# 12_RK3588_DDR_Controler.net
KiCad netlist of a schematic drawn in Altium Designer
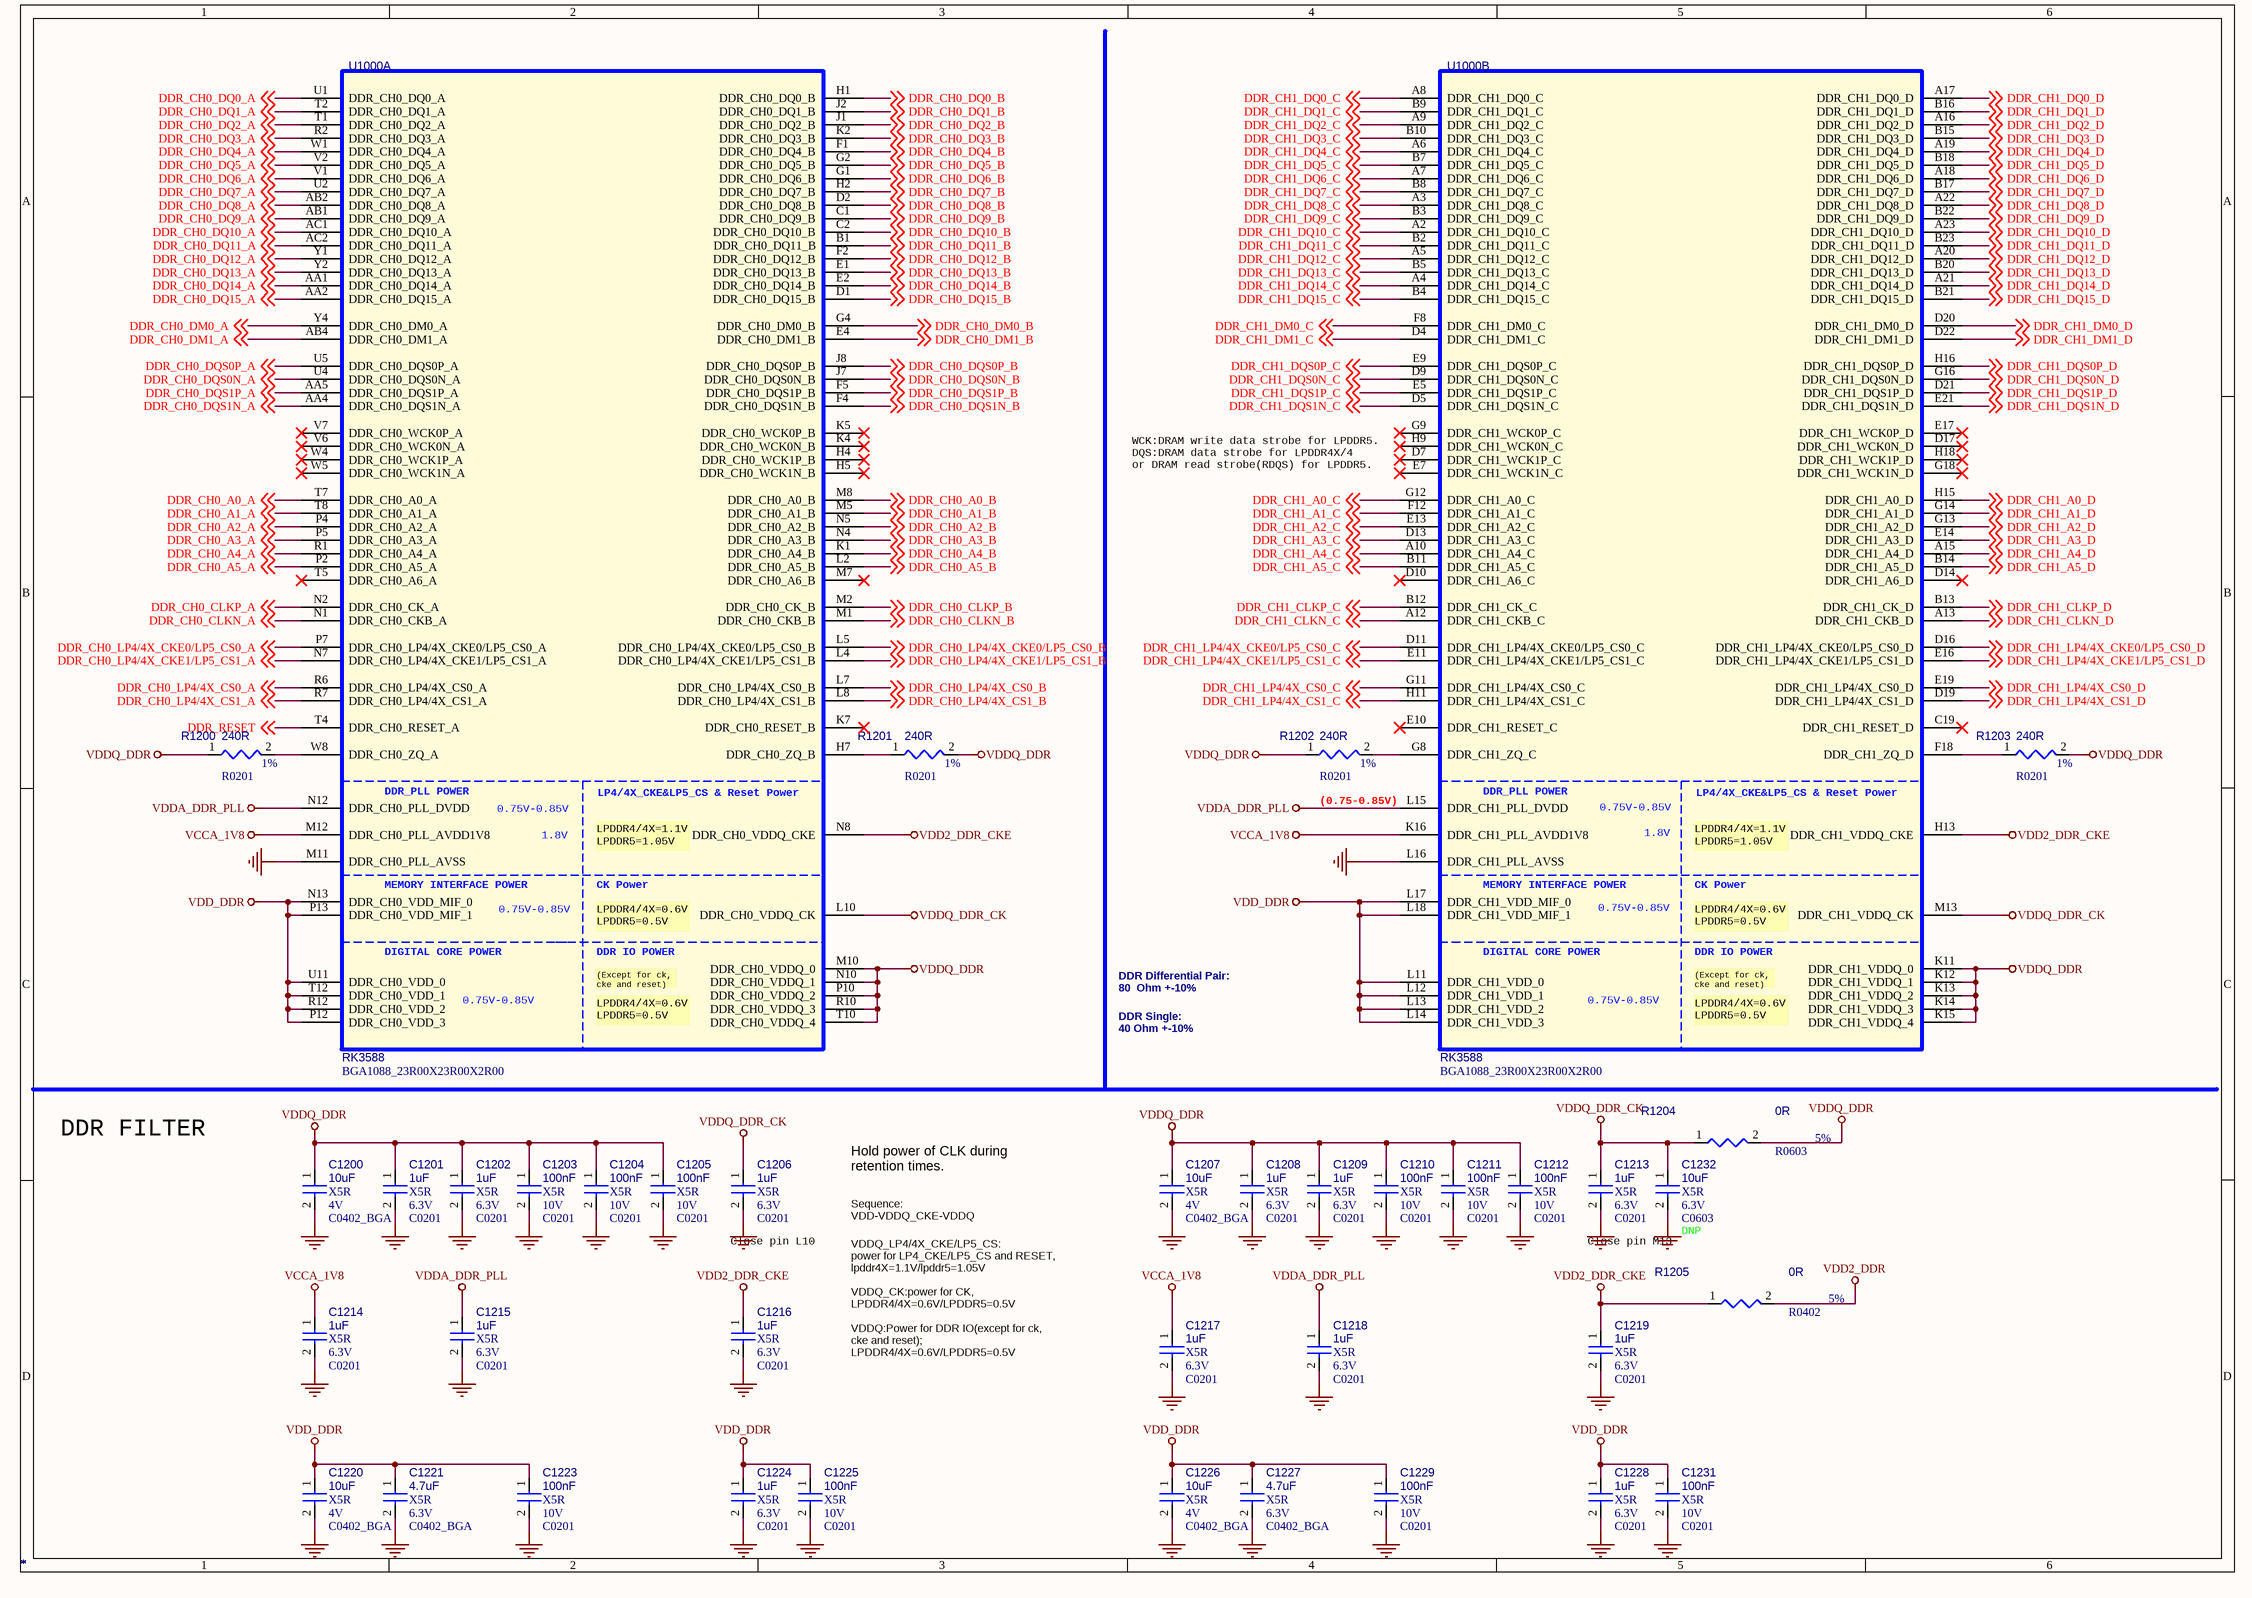
[diagram p0: 12.RK3588 DDR Controler.SchDoc]

(export (version "E")
  (design (tool "Eeschema 10.0.6"))
  (components
    (comp (ref "C1200")
      (value "*")
      (footprint "C0402_BGA")
      (description "cap,10.00uF,+/-20%,4V,X5R,C0402")
      (fields
        (field (name "VOLTAGE") "4V")
        (field (name "PCB FOOTPRINT") "C0402_BGA")
        (field (name "DIELECTRIC") "X5R")
        (field (name "MANUFACTURER") "YAGEO")
        (field (name "TOLERANCE") "20%")
        (field (name "ALTIUM_UNNAMED_1") "10uF")
        (field (name "CREATED BY") "JJJ")
      )
      (libsource (lib "*") (part "CAP NP"))
    )
    (comp (ref "C1201")
      (value "*")
      (footprint "C0201")
      (description "cap,1.00uF,+/-20%,6.3V,X5R,C0201")
      (fields
        (field (name "VOLTAGE") "6.3V")
        (field (name "PCB FOOTPRINT") "C0201")
        (field (name "DIELECTRIC") "X5R")
        (field (name "MANUFACTURER") "TDK")
        (field (name "TOLERANCE") "20%")
        (field (name "ALTIUM_UNNAMED_1") "1uF")
        (field (name "CREATED BY") "JJJ")
      )
      (libsource (lib "*") (part "CAP NP"))
    )
    (comp (ref "C1202")
      (value "*")
      (footprint "C0201")
      (description "cap,1.00uF,+/-20%,6.3V,X5R,C0201")
      (fields
        (field (name "VOLTAGE") "6.3V")
        (field (name "PCB FOOTPRINT") "C0201")
        (field (name "DIELECTRIC") "X5R")
        (field (name "TOLERANCE") "20%")
        (field (name "MANUFACTURER") "TDK")
        (field (name "ALTIUM_UNNAMED_1") "1uF")
        (field (name "CREATED BY") "JJJ")
      )
      (libsource (lib "*") (part "CAP NP"))
    )
    (comp (ref "C1203")
      (value "*")
      (footprint "C0201")
      (description "cap,100.00nF,+/-10%,10V,X5R,C0201")
      (fields
        (field (name "VOLTAGE") "10V")
        (field (name "PCB FOOTPRINT") "C0201")
        (field (name "DIELECTRIC") "X5R")
        (field (name "TOLERANCE") "10%")
        (field (name "MANUFACTURER") "TDK")
        (field (name "ALTIUM_UNNAMED_1") "100nF")
        (field (name "CREATED BY") "JJJ")
      )
      (libsource (lib "*") (part "CAP NP"))
    )
    (comp (ref "C1204")
      (value "*")
      (footprint "C0201")
      (description "cap,100.00nF,+/-10%,10V,X5R,C0201")
      (fields
        (field (name "VOLTAGE") "10V")
        (field (name "PCB FOOTPRINT") "C0201")
        (field (name "DIELECTRIC") "X5R")
        (field (name "TOLERANCE") "10%")
        (field (name "MANUFACTURER") "TDK")
        (field (name "ALTIUM_UNNAMED_1") "100nF")
        (field (name "CREATED BY") "JJJ")
      )
      (libsource (lib "*") (part "CAP NP"))
    )
    (comp (ref "C1205")
      (value "*")
      (footprint "C0201")
      (description "cap,100.00nF,+/-10%,10V,X5R,C0201")
      (fields
        (field (name "VOLTAGE") "10V")
        (field (name "PCB FOOTPRINT") "C0201")
        (field (name "DIELECTRIC") "X5R")
        (field (name "TOLERANCE") "10%")
        (field (name "MANUFACTURER") "TDK")
        (field (name "ALTIUM_UNNAMED_1") "100nF")
        (field (name "CREATED BY") "JJJ")
      )
      (libsource (lib "*") (part "CAP NP"))
    )
    (comp (ref "C1206")
      (value "*")
      (footprint "C0201")
      (description "cap,1.00uF,+/-20%,6.3V,X5R,C0201")
      (fields
        (field (name "VOLTAGE") "6.3V")
        (field (name "PCB FOOTPRINT") "C0201")
        (field (name "DIELECTRIC") "X5R")
        (field (name "MANUFACTURER") "TDK")
        (field (name "TOLERANCE") "20%")
        (field (name "ALTIUM_UNNAMED_1") "1uF")
        (field (name "CREATED BY") "JJJ")
      )
      (libsource (lib "*") (part "CAP NP"))
    )
    (comp (ref "C1207")
      (value "*")
      (footprint "C0402_BGA")
      (description "cap,10.00uF,+/-20%,4V,X5R,C0402")
      (fields
        (field (name "VOLTAGE") "4V")
        (field (name "PCB FOOTPRINT") "C0402_BGA")
        (field (name "DIELECTRIC") "X5R")
        (field (name "MANUFACTURER") "YAGEO")
        (field (name "TOLERANCE") "20%")
        (field (name "ALTIUM_UNNAMED_1") "10uF")
        (field (name "CREATED BY") "JJJ")
      )
      (libsource (lib "*") (part "CAP NP"))
    )
    (comp (ref "C1208")
      (value "*")
      (footprint "C0201")
      (description "cap,1.00uF,+/-20%,6.3V,X5R,C0201")
      (fields
        (field (name "VOLTAGE") "6.3V")
        (field (name "PCB FOOTPRINT") "C0201")
        (field (name "DIELECTRIC") "X5R")
        (field (name "MANUFACTURER") "TDK")
        (field (name "TOLERANCE") "20%")
        (field (name "ALTIUM_UNNAMED_1") "1uF")
        (field (name "CREATED BY") "JJJ")
      )
      (libsource (lib "*") (part "CAP NP"))
    )
    (comp (ref "C1209")
      (value "*")
      (footprint "C0201")
      (description "cap,1.00uF,+/-20%,6.3V,X5R,C0201")
      (fields
        (field (name "VOLTAGE") "6.3V")
        (field (name "PCB FOOTPRINT") "C0201")
        (field (name "DIELECTRIC") "X5R")
        (field (name "TOLERANCE") "20%")
        (field (name "MANUFACTURER") "TDK")
        (field (name "ALTIUM_UNNAMED_1") "1uF")
        (field (name "CREATED BY") "JJJ")
      )
      (libsource (lib "*") (part "CAP NP"))
    )
    (comp (ref "C1210")
      (value "*")
      (footprint "C0201")
      (description "cap,100.00nF,+/-10%,10V,X5R,C0201")
      (fields
        (field (name "VOLTAGE") "10V")
        (field (name "PCB FOOTPRINT") "C0201")
        (field (name "DIELECTRIC") "X5R")
        (field (name "TOLERANCE") "10%")
        (field (name "MANUFACTURER") "TDK")
        (field (name "ALTIUM_UNNAMED_1") "100nF")
        (field (name "CREATED BY") "JJJ")
      )
      (libsource (lib "*") (part "CAP NP"))
    )
    (comp (ref "C1211")
      (value "*")
      (footprint "C0201")
      (description "cap,100.00nF,+/-10%,10V,X5R,C0201")
      (fields
        (field (name "VOLTAGE") "10V")
        (field (name "PCB FOOTPRINT") "C0201")
        (field (name "DIELECTRIC") "X5R")
        (field (name "TOLERANCE") "10%")
        (field (name "MANUFACTURER") "TDK")
        (field (name "ALTIUM_UNNAMED_1") "100nF")
        (field (name "CREATED BY") "JJJ")
      )
      (libsource (lib "*") (part "CAP NP"))
    )
    (comp (ref "C1212")
      (value "*")
      (footprint "C0201")
      (description "cap,100.00nF,+/-10%,10V,X5R,C0201")
      (fields
        (field (name "VOLTAGE") "10V")
        (field (name "PCB FOOTPRINT") "C0201")
        (field (name "DIELECTRIC") "X5R")
        (field (name "TOLERANCE") "10%")
        (field (name "MANUFACTURER") "TDK")
        (field (name "ALTIUM_UNNAMED_1") "100nF")
        (field (name "CREATED BY") "JJJ")
      )
      (libsource (lib "*") (part "CAP NP"))
    )
    (comp (ref "C1213")
      (value "*")
      (footprint "C0201")
      (description "cap,1.00uF,+/-20%,6.3V,X5R,C0201")
      (fields
        (field (name "VOLTAGE") "6.3V")
        (field (name "PCB FOOTPRINT") "C0201")
        (field (name "DIELECTRIC") "X5R")
        (field (name "MANUFACTURER") "TDK")
        (field (name "TOLERANCE") "20%")
        (field (name "ALTIUM_UNNAMED_1") "1uF")
        (field (name "CREATED BY") "JJJ")
      )
      (libsource (lib "*") (part "CAP NP"))
    )
    (comp (ref "C1214")
      (value "*")
      (footprint "C0201")
      (description "cap,1.00uF,+/-20%,6.3V,X5R,C0201")
      (fields
        (field (name "VOLTAGE") "6.3V")
        (field (name "PCB FOOTPRINT") "C0201")
        (field (name "DIELECTRIC") "X5R")
        (field (name "TOLERANCE") "20%")
        (field (name "MANUFACTURER") "TDK")
        (field (name "ALTIUM_UNNAMED_1") "1uF")
        (field (name "CREATED BY") "JJJ")
      )
      (libsource (lib "*") (part "CAP NP"))
    )
    (comp (ref "C1215")
      (value "*")
      (footprint "C0201")
      (description "cap,1.00uF,+/-20%,6.3V,X5R,C0201")
      (fields
        (field (name "VOLTAGE") "6.3V")
        (field (name "PCB FOOTPRINT") "C0201")
        (field (name "DIELECTRIC") "X5R")
        (field (name "MANUFACTURER") "TDK")
        (field (name "TOLERANCE") "20%")
        (field (name "ALTIUM_UNNAMED_1") "1uF")
        (field (name "CREATED BY") "JJJ")
      )
      (libsource (lib "*") (part "CAP NP"))
    )
    (comp (ref "C1216")
      (value "*")
      (footprint "C0201")
      (description "cap,1.00uF,+/-20%,6.3V,X5R,C0201")
      (fields
        (field (name "VOLTAGE") "6.3V")
        (field (name "PCB FOOTPRINT") "C0201")
        (field (name "DIELECTRIC") "X5R")
        (field (name "MANUFACTURER") "TDK")
        (field (name "TOLERANCE") "20%")
        (field (name "ALTIUM_UNNAMED_1") "1uF")
        (field (name "CREATED BY") "JJJ")
      )
      (libsource (lib "*") (part "CAP NP"))
    )
    (comp (ref "C1217")
      (value "*")
      (footprint "C0201")
      (description "cap,1.00uF,+/-20%,6.3V,X5R,C0201")
      (fields
        (field (name "VOLTAGE") "6.3V")
        (field (name "PCB FOOTPRINT") "C0201")
        (field (name "DIELECTRIC") "X5R")
        (field (name "MANUFACTURER") "TDK")
        (field (name "TOLERANCE") "20%")
        (field (name "ALTIUM_UNNAMED_1") "1uF")
        (field (name "CREATED BY") "JJJ")
      )
      (libsource (lib "*") (part "CAP NP"))
    )
    (comp (ref "C1218")
      (value "*")
      (footprint "C0201")
      (description "cap,1.00uF,+/-20%,6.3V,X5R,C0201")
      (fields
        (field (name "VOLTAGE") "6.3V")
        (field (name "PCB FOOTPRINT") "C0201")
        (field (name "DIELECTRIC") "X5R")
        (field (name "TOLERANCE") "20%")
        (field (name "MANUFACTURER") "TDK")
        (field (name "ALTIUM_UNNAMED_1") "1uF")
        (field (name "CREATED BY") "JJJ")
      )
      (libsource (lib "*") (part "CAP NP"))
    )
    (comp (ref "C1219")
      (value "*")
      (footprint "C0201")
      (description "cap,1.00uF,+/-20%,6.3V,X5R,C0201")
      (fields
        (field (name "VOLTAGE") "6.3V")
        (field (name "PCB FOOTPRINT") "C0201")
        (field (name "DIELECTRIC") "X5R")
        (field (name "TOLERANCE") "20%")
        (field (name "MANUFACTURER") "TDK")
        (field (name "ALTIUM_UNNAMED_1") "1uF")
        (field (name "CREATED BY") "JJJ")
      )
      (libsource (lib "*") (part "CAP NP"))
    )
    (comp (ref "C1220")
      (value "*")
      (footprint "C0402_BGA")
      (description "cap,10.00uF,+/-20%,4V,X5R,C0402")
      (fields
        (field (name "VOLTAGE") "4V")
        (field (name "PCB FOOTPRINT") "C0402_BGA")
        (field (name "DIELECTRIC") "X5R")
        (field (name "TOLERANCE") "20%")
        (field (name "MANUFACTURER") "YAGEO")
        (field (name "ALTIUM_UNNAMED_1") "10uF")
        (field (name "CREATED BY") "JJJ")
      )
      (libsource (lib "*") (part "CAP NP"))
    )
    (comp (ref "C1221")
      (value "*")
      (footprint "C0402_BGA")
      (description "cap,4.70uF,+/-10%,6.3V,X5R,C0402")
      (fields
        (field (name "VOLTAGE") "6.3V")
        (field (name "PCB FOOTPRINT") "C0402_BGA")
        (field (name "DIELECTRIC") "X5R")
        (field (name "MANUFACTURER") "TDK")
        (field (name "TOLERANCE") "10%")
        (field (name "ALTIUM_UNNAMED_1") "4.7uF")
        (field (name "CREATED BY") "JJJ")
      )
      (libsource (lib "*") (part "CAP NP"))
    )
    (comp (ref "C1223")
      (value "*")
      (footprint "C0201")
      (description "cap,100.00nF,+/-10%,10V,X5R,C0201")
      (fields
        (field (name "VOLTAGE") "10V")
        (field (name "PCB FOOTPRINT") "C0201")
        (field (name "DIELECTRIC") "X5R")
        (field (name "TOLERANCE") "10%")
        (field (name "MANUFACTURER") "TDK")
        (field (name "ALTIUM_UNNAMED_1") "100nF")
        (field (name "CREATED BY") "JJJ")
      )
      (libsource (lib "*") (part "CAP NP"))
    )
    (comp (ref "C1224")
      (value "*")
      (footprint "C0201")
      (description "cap,1.00uF,+/-20%,6.3V,X5R,C0201")
      (fields
        (field (name "VOLTAGE") "6.3V")
        (field (name "PCB FOOTPRINT") "C0201")
        (field (name "DIELECTRIC") "X5R")
        (field (name "MANUFACTURER") "TDK")
        (field (name "TOLERANCE") "20%")
        (field (name "ALTIUM_UNNAMED_1") "1uF")
        (field (name "CREATED BY") "JJJ")
      )
      (libsource (lib "*") (part "CAP NP"))
    )
    (comp (ref "C1225")
      (value "*")
      (footprint "C0201")
      (description "cap,100.00nF,+/-10%,10V,X5R,C0201")
      (fields
        (field (name "VOLTAGE") "10V")
        (field (name "PCB FOOTPRINT") "C0201")
        (field (name "DIELECTRIC") "X5R")
        (field (name "TOLERANCE") "10%")
        (field (name "MANUFACTURER") "TDK")
        (field (name "ALTIUM_UNNAMED_1") "100nF")
        (field (name "CREATED BY") "JJJ")
      )
      (libsource (lib "*") (part "CAP NP"))
    )
    (comp (ref "C1226")
      (value "*")
      (footprint "C0402_BGA")
      (description "cap,10.00uF,+/-20%,4V,X5R,C0402")
      (fields
        (field (name "VOLTAGE") "4V")
        (field (name "PCB FOOTPRINT") "C0402_BGA")
        (field (name "DIELECTRIC") "X5R")
        (field (name "TOLERANCE") "20%")
        (field (name "MANUFACTURER") "YAGEO")
        (field (name "ALTIUM_UNNAMED_1") "10uF")
        (field (name "CREATED BY") "JJJ")
      )
      (libsource (lib "*") (part "CAP NP"))
    )
    (comp (ref "C1227")
      (value "*")
      (footprint "C0402_BGA")
      (description "cap,4.70uF,+/-10%,6.3V,X5R,C0402")
      (fields
        (field (name "VOLTAGE") "6.3V")
        (field (name "PCB FOOTPRINT") "C0402_BGA")
        (field (name "DIELECTRIC") "X5R")
        (field (name "MANUFACTURER") "TDK")
        (field (name "TOLERANCE") "10%")
        (field (name "ALTIUM_UNNAMED_1") "4.7uF")
        (field (name "CREATED BY") "JJJ")
      )
      (libsource (lib "*") (part "CAP NP"))
    )
    (comp (ref "C1228")
      (value "*")
      (footprint "C0201")
      (description "cap,1.00uF,+/-20%,6.3V,X5R,C0201")
      (fields
        (field (name "VOLTAGE") "6.3V")
        (field (name "PCB FOOTPRINT") "C0201")
        (field (name "DIELECTRIC") "X5R")
        (field (name "TOLERANCE") "20%")
        (field (name "MANUFACTURER") "TDK")
        (field (name "ALTIUM_UNNAMED_1") "1uF")
        (field (name "CREATED BY") "JJJ")
      )
      (libsource (lib "*") (part "CAP NP"))
    )
    (comp (ref "C1229")
      (value "*")
      (footprint "C0201")
      (description "cap,100.00nF,+/-10%,10V,X5R,C0201")
      (fields
        (field (name "VOLTAGE") "10V")
        (field (name "PCB FOOTPRINT") "C0201")
        (field (name "DIELECTRIC") "X5R")
        (field (name "TOLERANCE") "10%")
        (field (name "MANUFACTURER") "TDK")
        (field (name "ALTIUM_UNNAMED_1") "100nF")
        (field (name "CREATED BY") "JJJ")
      )
      (libsource (lib "*") (part "CAP NP"))
    )
    (comp (ref "C1231")
      (value "*")
      (footprint "C0201")
      (description "cap,100.00nF,+/-10%,10V,X5R,C0201")
      (fields
        (field (name "VOLTAGE") "10V")
        (field (name "PCB FOOTPRINT") "C0201")
        (field (name "DIELECTRIC") "X5R")
        (field (name "TOLERANCE") "10%")
        (field (name "MANUFACTURER") "TDK")
        (field (name "ALTIUM_UNNAMED_1") "100nF")
        (field (name "CREATED BY") "JJJ")
      )
      (libsource (lib "*") (part "CAP NP"))
    )
    (comp (ref "C1232")
      (value "*")
      (footprint "C0603")
      (description "cap,10.00uF,+/-10%,6.3V,X5R,C0603")
      (fields
        (field (name "VOLTAGE") "6.3V")
        (field (name "PCB FOOTPRINT") "C0603")
        (field (name "DIELECTRIC") "X5R")
        (field (name "OPTION") "DNP")
        (field (name "TOLERANCE") "10%")
        (field (name "MANUFACTURER") "TDK")
        (field (name "ALTIUM_UNNAMED_1") "10uF")
        (field (name "CREATED BY") "JJJ")
      )
      (libsource (lib "*") (part "CAP NP"))
    )
    (comp (ref "R1200")
      (value "*")
      (footprint "R0402")
      (description "НЁУГєсД¤µзЧи,240R,+/-1%,R0201,1/20W.")
      (fields
        (field (name "PCB FOOTPRINT") "R0201")
        (field (name "TOLERANCE") "1%")
        (field (name "MANUFACTURER") "YAGEO")
        (field (name "ALTIUM_UNNAMED_1") "240R")
        (field (name "CREATED BY") "YTL")
      )
      (libsource (lib "*") (part "RESISTOR_Dup1"))
    )
    (comp (ref "R1201")
      (value "*")
      (footprint "R0402")
      (description "НЁУГєсД¤µзЧи,240R,+/-1%,R0201,1/20W.")
      (fields
        (field (name "PCB FOOTPRINT") "R0201")
        (field (name "TOLERANCE") "1%")
        (field (name "MANUFACTURER") "YAGEO")
        (field (name "ALTIUM_UNNAMED_1") "240R")
        (field (name "CREATED BY") "YTL")
      )
      (libsource (lib "*") (part "RESISTOR_Dup1"))
    )
    (comp (ref "R1202")
      (value "*")
      (footprint "R0402")
      (description "НЁУГєсД¤µзЧи,240R,+/-1%,R0201,1/20W.")
      (fields
        (field (name "PCB FOOTPRINT") "R0201")
        (field (name "TOLERANCE") "1%")
        (field (name "MANUFACTURER") "YAGEO")
        (field (name "ALTIUM_UNNAMED_1") "240R")
        (field (name "CREATED BY") "YTL")
      )
      (libsource (lib "*") (part "RESISTOR_Dup1"))
    )
    (comp (ref "R1203")
      (value "*")
      (footprint "R0402")
      (description "НЁУГєсД¤µзЧи,240R,+/-1%,R0201,1/20W.")
      (fields
        (field (name "PCB FOOTPRINT") "R0201")
        (field (name "TOLERANCE") "1%")
        (field (name "MANUFACTURER") "YAGEO")
        (field (name "ALTIUM_UNNAMED_1") "240R")
        (field (name "CREATED BY") "YTL")
      )
      (libsource (lib "*") (part "RESISTOR_Dup1"))
    )
    (comp (ref "R1204")
      (value "*")
      (footprint "R0402")
      (description "НЁУГєсД¤µзЧи,0R,+/-5%,R0603,1/10W.")
      (fields
        (field (name "PCB FOOTPRINT") "R0603")
        (field (name "TOLERANCE") "5%")
        (field (name "MANUFACTURER") "YAGEO")
        (field (name "ALTIUM_UNNAMED_1") "0R")
        (field (name "CREATED BY") "YTL")
      )
      (libsource (lib "*") (part "RESISTOR_Dup1"))
    )
    (comp (ref "R1205")
      (value "*")
      (footprint "R0402")
      (description "НЁУГєсД¤µзЧи,0R,+/-5%,R0402,1/16W.")
      (fields
        (field (name "PCB FOOTPRINT") "R0402")
        (field (name "TOLERANCE") "5%")
        (field (name "MANUFACTURER") "YAGEO")
        (field (name "ALTIUM_UNNAMED_1") "0R")
        (field (name "CREATED BY") "YTL")
      )
      (libsource (lib "*") (part "RESISTOR_Dup1"))
    )
    (comp (ref "U1000")
      (value "*")
      (footprint "BGA1088_23R00X23R00X2R00")
      (description "ROCKCHIP SOC")
      (fields
        (field (name "MANUFACTURER") "Rockchip (ИрРѕОў)")
        (field (name "PCB FOOTPRINT") "BGA1088_23R00X23R00X2R00")
        (field (name "ALTIUM_UNNAMED_1") "RK3588")
        (field (name "CREATED BY") "YWQ")
      )
      (libsource (lib "*") (part "SOC_RK3588"))
    )
  )
  (nets
    (net (code "1") (name "DDR_CH0_A0_A") (class "Default")
      (node (ref "U1000") (pin "T7") (pinfunction "DDR_CH0_A0_A_T7") (pintype "passive"))
    )
    (net (code "2") (name "DDR_CH0_A0_B") (class "Default")
      (node (ref "U1000") (pin "M8") (pinfunction "DDR_CH0_A0_B_M8") (pintype "passive"))
    )
    (net (code "3") (name "DDR_CH0_A1_A") (class "Default")
      (node (ref "U1000") (pin "T8") (pinfunction "DDR_CH0_A1_A_T8") (pintype "passive"))
    )
    (net (code "4") (name "DDR_CH0_A1_B") (class "Default")
      (node (ref "U1000") (pin "M5") (pinfunction "DDR_CH0_A1_B_M5") (pintype "passive"))
    )
    (net (code "5") (name "DDR_CH0_A2_A") (class "Default")
      (node (ref "U1000") (pin "P4") (pinfunction "DDR_CH0_A2_A_P4") (pintype "passive"))
    )
    (net (code "6") (name "DDR_CH0_A2_B") (class "Default")
      (node (ref "U1000") (pin "N5") (pinfunction "DDR_CH0_A2_B_N5") (pintype "passive"))
    )
    (net (code "7") (name "DDR_CH0_A3_A") (class "Default")
      (node (ref "U1000") (pin "P5") (pinfunction "DDR_CH0_A3_A_P5") (pintype "passive"))
    )
    (net (code "8") (name "DDR_CH0_A3_B") (class "Default")
      (node (ref "U1000") (pin "N4") (pinfunction "DDR_CH0_A3_B_N4") (pintype "passive"))
    )
    (net (code "9") (name "DDR_CH0_A4_A") (class "Default")
      (node (ref "U1000") (pin "R1") (pinfunction "DDR_CH0_A4_A_R1") (pintype "passive"))
    )
    (net (code "10") (name "DDR_CH0_A4_B") (class "Default")
      (node (ref "U1000") (pin "K1") (pinfunction "DDR_CH0_A4_B_K1") (pintype "passive"))
    )
    (net (code "11") (name "DDR_CH0_A5_A") (class "Default")
      (node (ref "U1000") (pin "P2") (pinfunction "DDR_CH0_A5_A_P2") (pintype "passive"))
    )
    (net (code "12") (name "DDR_CH0_A5_B") (class "Default")
      (node (ref "U1000") (pin "L2") (pinfunction "DDR_CH0_A5_B_L2") (pintype "passive"))
    )
    (net (code "13") (name "DDR_CH0_CLKN_A") (class "Default")
      (node (ref "U1000") (pin "N1") (pinfunction "DDR_CH0_CKB_A_N1") (pintype "passive"))
    )
    (net (code "14") (name "DDR_CH0_CLKN_B") (class "Default")
      (node (ref "U1000") (pin "M1") (pinfunction "DDR_CH0_CKB_B_M1") (pintype "passive"))
    )
    (net (code "15") (name "DDR_CH0_CLKP_A") (class "Default")
      (node (ref "U1000") (pin "N2") (pinfunction "DDR_CH0_CK_A_N2") (pintype "passive"))
    )
    (net (code "16") (name "DDR_CH0_CLKP_B") (class "Default")
      (node (ref "U1000") (pin "M2") (pinfunction "DDR_CH0_CK_B_M2") (pintype "passive"))
    )
    (net (code "17") (name "DDR_CH0_DM0_A") (class "Default")
      (node (ref "U1000") (pin "Y4") (pinfunction "DDR_CH0_DM0_A_Y4") (pintype "passive"))
    )
    (net (code "18") (name "DDR_CH0_DM0_B") (class "Default")
      (node (ref "U1000") (pin "G4") (pinfunction "DDR_CH0_DM0_B_G4") (pintype "passive"))
    )
    (net (code "19") (name "DDR_CH0_DM1_A") (class "Default")
      (node (ref "U1000") (pin "AB4") (pinfunction "DDR_CH0_DM1_A_AB4") (pintype "passive"))
    )
    (net (code "20") (name "DDR_CH0_DM1_B") (class "Default")
      (node (ref "U1000") (pin "E4") (pinfunction "DDR_CH0_DM1_B_E4") (pintype "passive"))
    )
    (net (code "21") (name "DDR_CH0_DQ0_A") (class "Default")
      (node (ref "U1000") (pin "U1") (pinfunction "DDR_CH0_DQ0_A_U1") (pintype "passive"))
    )
    (net (code "22") (name "DDR_CH0_DQ0_B") (class "Default")
      (node (ref "U1000") (pin "H1") (pinfunction "DDR_CH0_DQ0_B_H1") (pintype "passive"))
    )
    (net (code "23") (name "DDR_CH0_DQ1_A") (class "Default")
      (node (ref "U1000") (pin "T2") (pinfunction "DDR_CH0_DQ1_A_T2") (pintype "passive"))
    )
    (net (code "24") (name "DDR_CH0_DQ1_B") (class "Default")
      (node (ref "U1000") (pin "J2") (pinfunction "DDR_CH0_DQ1_B_J2") (pintype "passive"))
    )
    (net (code "25") (name "DDR_CH0_DQ2_A") (class "Default")
      (node (ref "U1000") (pin "T1") (pinfunction "DDR_CH0_DQ2_A_T1") (pintype "passive"))
    )
    (net (code "26") (name "DDR_CH0_DQ2_B") (class "Default")
      (node (ref "U1000") (pin "J1") (pinfunction "DDR_CH0_DQ2_B_J1") (pintype "passive"))
    )
    (net (code "27") (name "DDR_CH0_DQ3_A") (class "Default")
      (node (ref "U1000") (pin "R2") (pinfunction "DDR_CH0_DQ3_A_R2") (pintype "passive"))
    )
    (net (code "28") (name "DDR_CH0_DQ3_B") (class "Default")
      (node (ref "U1000") (pin "K2") (pinfunction "DDR_CH0_DQ3_B_K2") (pintype "passive"))
    )
    (net (code "29") (name "DDR_CH0_DQ4_A") (class "Default")
      (node (ref "U1000") (pin "W1") (pinfunction "DDR_CH0_DQ4_A_W1") (pintype "passive"))
    )
    (net (code "30") (name "DDR_CH0_DQ4_B") (class "Default")
      (node (ref "U1000") (pin "F1") (pinfunction "DDR_CH0_DQ4_B_F1") (pintype "passive"))
    )
    (net (code "31") (name "DDR_CH0_DQ5_A") (class "Default")
      (node (ref "U1000") (pin "V2") (pinfunction "DDR_CH0_DQ5_A_V2") (pintype "passive"))
    )
    (net (code "32") (name "DDR_CH0_DQ5_B") (class "Default")
      (node (ref "U1000") (pin "G2") (pinfunction "DDR_CH0_DQ5_B_G2") (pintype "passive"))
    )
    (net (code "33") (name "DDR_CH0_DQ6_A") (class "Default")
      (node (ref "U1000") (pin "V1") (pinfunction "DDR_CH0_DQ6_A_V1") (pintype "passive"))
    )
    (net (code "34") (name "DDR_CH0_DQ6_B") (class "Default")
      (node (ref "U1000") (pin "G1") (pinfunction "DDR_CH0_DQ6_B_G1") (pintype "passive"))
    )
    (net (code "35") (name "DDR_CH0_DQ7_A") (class "Default")
      (node (ref "U1000") (pin "U2") (pinfunction "DDR_CH0_DQ7_A_U2") (pintype "passive"))
    )
    (net (code "36") (name "DDR_CH0_DQ7_B") (class "Default")
      (node (ref "U1000") (pin "H2") (pinfunction "DDR_CH0_DQ7_B_H2") (pintype "passive"))
    )
    (net (code "37") (name "DDR_CH0_DQ8_A") (class "Default")
      (node (ref "U1000") (pin "AB2") (pinfunction "DDR_CH0_DQ8_A_AB2") (pintype "passive"))
    )
    (net (code "38") (name "DDR_CH0_DQ8_B") (class "Default")
      (node (ref "U1000") (pin "D2") (pinfunction "DDR_CH0_DQ8_B_D2") (pintype "passive"))
    )
    (net (code "39") (name "DDR_CH0_DQ9_A") (class "Default")
      (node (ref "U1000") (pin "AB1") (pinfunction "DDR_CH0_DQ9_A_AB1") (pintype "passive"))
    )
    (net (code "40") (name "DDR_CH0_DQ9_B") (class "Default")
      (node (ref "U1000") (pin "C1") (pinfunction "DDR_CH0_DQ9_B_C1") (pintype "passive"))
    )
    (net (code "41") (name "DDR_CH0_DQ10_A") (class "Default")
      (node (ref "U1000") (pin "AC1") (pinfunction "DDR_CH0_DQ10_A_AC1") (pintype "passive"))
    )
    (net (code "42") (name "DDR_CH0_DQ10_B") (class "Default")
      (node (ref "U1000") (pin "C2") (pinfunction "DDR_CH0_DQ10_B_C2") (pintype "passive"))
    )
    (net (code "43") (name "DDR_CH0_DQ11_A") (class "Default")
      (node (ref "U1000") (pin "AC2") (pinfunction "DDR_CH0_DQ11_A_AC2") (pintype "passive"))
    )
    (net (code "44") (name "DDR_CH0_DQ11_B") (class "Default")
      (node (ref "U1000") (pin "B1") (pinfunction "DDR_CH0_DQ11_B_B1") (pintype "passive"))
    )
    (net (code "45") (name "DDR_CH0_DQ12_A") (class "Default")
      (node (ref "U1000") (pin "Y1") (pinfunction "DDR_CH0_DQ12_A_Y1") (pintype "passive"))
    )
    (net (code "46") (name "DDR_CH0_DQ12_B") (class "Default")
      (node (ref "U1000") (pin "F2") (pinfunction "DDR_CH0_DQ12_B_F2") (pintype "passive"))
    )
    (net (code "47") (name "DDR_CH0_DQ13_A") (class "Default")
      (node (ref "U1000") (pin "Y2") (pinfunction "DDR_CH0_DQ13_A_Y2") (pintype "passive"))
    )
    (net (code "48") (name "DDR_CH0_DQ13_B") (class "Default")
      (node (ref "U1000") (pin "E1") (pinfunction "DDR_CH0_DQ13_B_E1") (pintype "passive"))
    )
    (net (code "49") (name "DDR_CH0_DQ14_A") (class "Default")
      (node (ref "U1000") (pin "AA1") (pinfunction "DDR_CH0_DQ14_A_AA1") (pintype "passive"))
    )
    (net (code "50") (name "DDR_CH0_DQ14_B") (class "Default")
      (node (ref "U1000") (pin "E2") (pinfunction "DDR_CH0_DQ14_B_E2") (pintype "passive"))
    )
    (net (code "51") (name "DDR_CH0_DQ15_A") (class "Default")
      (node (ref "U1000") (pin "AA2") (pinfunction "DDR_CH0_DQ15_A_AA2") (pintype "passive"))
    )
    (net (code "52") (name "DDR_CH0_DQ15_B") (class "Default")
      (node (ref "U1000") (pin "D1") (pinfunction "DDR_CH0_DQ15_B_D1") (pintype "passive"))
    )
    (net (code "53") (name "DDR_CH0_DQS0N_A") (class "Default")
      (node (ref "U1000") (pin "U4") (pinfunction "DDR_CH0_DQS0N_A_U4") (pintype "passive"))
    )
    (net (code "54") (name "DDR_CH0_DQS0N_B") (class "Default")
      (node (ref "U1000") (pin "J7") (pinfunction "DDR_CH0_DQS0N_B_J7") (pintype "passive"))
    )
    (net (code "55") (name "DDR_CH0_DQS0P_A") (class "Default")
      (node (ref "U1000") (pin "U5") (pinfunction "DDR_CH0_DQS0P_A_U5") (pintype "passive"))
    )
    (net (code "56") (name "DDR_CH0_DQS0P_B") (class "Default")
      (node (ref "U1000") (pin "J8") (pinfunction "DDR_CH0_DQS0P_B_J8") (pintype "passive"))
    )
    (net (code "57") (name "DDR_CH0_DQS1N_A") (class "Default")
      (node (ref "U1000") (pin "AA4") (pinfunction "DDR_CH0_DQS1N_A_AA4") (pintype "passive"))
    )
    (net (code "58") (name "DDR_CH0_DQS1N_B") (class "Default")
      (node (ref "U1000") (pin "F4") (pinfunction "DDR_CH0_DQS1N_B_F4") (pintype "passive"))
    )
    (net (code "59") (name "DDR_CH0_DQS1P_A") (class "Default")
      (node (ref "U1000") (pin "AA5") (pinfunction "DDR_CH0_DQS1P_A_AA5") (pintype "passive"))
    )
    (net (code "60") (name "DDR_CH0_DQS1P_B") (class "Default")
      (node (ref "U1000") (pin "F5") (pinfunction "DDR_CH0_DQS1P_B_F5") (pintype "passive"))
    )
    (net (code "61") (name "DDR_CH0_LP4{slash}4X_CKE0{slash}LP5_CS0_A") (class "Default")
      (node (ref "U1000") (pin "P7") (pinfunction "DDR_CH0_LP4/4X_CKE0/LP5_CS0_A_P7") (pintype "passive"))
    )
    (net (code "62") (name "DDR_CH0_LP4{slash}4X_CKE0{slash}LP5_CS0_B") (class "Default")
      (node (ref "U1000") (pin "L5") (pinfunction "DDR_CH0_LP4/4X_CKE0/LP5_CS0_B_L5") (pintype "passive"))
    )
    (net (code "63") (name "DDR_CH0_LP4{slash}4X_CKE1{slash}LP5_CS1_A") (class "Default")
      (node (ref "U1000") (pin "N7") (pinfunction "DDR_CH0_LP4/4X_CKE1/LP5_CS1_A_N7") (pintype "passive"))
    )
    (net (code "64") (name "DDR_CH0_LP4{slash}4X_CKE1{slash}LP5_CS1_B") (class "Default")
      (node (ref "U1000") (pin "L4") (pinfunction "DDR_CH0_LP4/4X_CKE1/LP5_CS1_B_L4") (pintype "passive"))
    )
    (net (code "65") (name "DDR_CH0_LP4{slash}4X_CS0_A") (class "Default")
      (node (ref "U1000") (pin "R6") (pinfunction "DDR_CH0_LP4/4X_CS0_A_R6") (pintype "passive"))
    )
    (net (code "66") (name "DDR_CH0_LP4{slash}4X_CS0_B") (class "Default")
      (node (ref "U1000") (pin "L7") (pinfunction "DDR_CH0_LP4/4X_CS0_B_L7") (pintype "passive"))
    )
    (net (code "67") (name "DDR_CH0_LP4{slash}4X_CS1_A") (class "Default")
      (node (ref "U1000") (pin "R7") (pinfunction "DDR_CH0_LP4/4X_CS1_A_R7") (pintype "passive"))
    )
    (net (code "68") (name "DDR_CH0_LP4{slash}4X_CS1_B") (class "Default")
      (node (ref "U1000") (pin "L8") (pinfunction "DDR_CH0_LP4/4X_CS1_B_L8") (pintype "passive"))
    )
    (net (code "69") (name "DDR_CH1_A0_C") (class "Default")
      (node (ref "U1000") (pin "G12") (pinfunction "DDR_CH1_A0_C_G12") (pintype "passive"))
    )
    (net (code "70") (name "DDR_CH1_A0_D") (class "Default")
      (node (ref "U1000") (pin "H15") (pinfunction "DDR_CH1_A0_D_H15") (pintype "passive"))
    )
    (net (code "71") (name "DDR_CH1_A1_C") (class "Default")
      (node (ref "U1000") (pin "F12") (pinfunction "DDR_CH1_A1_C_F12") (pintype "passive"))
    )
    (net (code "72") (name "DDR_CH1_A1_D") (class "Default")
      (node (ref "U1000") (pin "G14") (pinfunction "DDR_CH1_A1_D_G14") (pintype "passive"))
    )
    (net (code "73") (name "DDR_CH1_A2_C") (class "Default")
      (node (ref "U1000") (pin "E13") (pinfunction "DDR_CH1_A2_C_E13") (pintype "passive"))
    )
    (net (code "74") (name "DDR_CH1_A2_D") (class "Default")
      (node (ref "U1000") (pin "G13") (pinfunction "DDR_CH1_A2_D_G13") (pintype "passive"))
    )
    (net (code "75") (name "DDR_CH1_A3_C") (class "Default")
      (node (ref "U1000") (pin "D13") (pinfunction "DDR_CH1_A3_C_D13") (pintype "passive"))
    )
    (net (code "76") (name "DDR_CH1_A3_D") (class "Default")
      (node (ref "U1000") (pin "E14") (pinfunction "DDR_CH1_A3_D_E14") (pintype "passive"))
    )
    (net (code "77") (name "DDR_CH1_A4_C") (class "Default")
      (node (ref "U1000") (pin "A10") (pinfunction "DDR_CH1_A4_C_A10") (pintype "passive"))
    )
    (net (code "78") (name "DDR_CH1_A4_D") (class "Default")
      (node (ref "U1000") (pin "A15") (pinfunction "DDR_CH1_A4_D_A15") (pintype "passive"))
    )
    (net (code "79") (name "DDR_CH1_A5_C") (class "Default")
      (node (ref "U1000") (pin "B11") (pinfunction "DDR_CH1_A5_C_B11") (pintype "passive"))
    )
    (net (code "80") (name "DDR_CH1_A5_D") (class "Default")
      (node (ref "U1000") (pin "B14") (pinfunction "DDR_CH1_A5_D_B14") (pintype "passive"))
    )
    (net (code "81") (name "DDR_CH1_CLKN_C") (class "Default")
      (node (ref "U1000") (pin "A12") (pinfunction "DDR_CH1_CKB_C_A12") (pintype "passive"))
    )
    (net (code "82") (name "DDR_CH1_CLKN_D") (class "Default")
      (node (ref "U1000") (pin "A13") (pinfunction "DDR_CH1_CKB_D_A13") (pintype "passive"))
    )
    (net (code "83") (name "DDR_CH1_CLKP_C") (class "Default")
      (node (ref "U1000") (pin "B12") (pinfunction "DDR_CH1_CK_C_B12") (pintype "passive"))
    )
    (net (code "84") (name "DDR_CH1_CLKP_D") (class "Default")
      (node (ref "U1000") (pin "B13") (pinfunction "DDR_CH1_CK_D_B13") (pintype "passive"))
    )
    (net (code "85") (name "DDR_CH1_DM0_C") (class "Default")
      (node (ref "U1000") (pin "F8") (pinfunction "DDR_CH1_DM0_C_F8") (pintype "passive"))
    )
    (net (code "86") (name "DDR_CH1_DM0_D") (class "Default")
      (node (ref "U1000") (pin "D20") (pinfunction "DDR_CH1_DM0_D_D20") (pintype "passive"))
    )
    (net (code "87") (name "DDR_CH1_DM1_C") (class "Default")
      (node (ref "U1000") (pin "D4") (pinfunction "DDR_CH1_DM1_C_D4") (pintype "passive"))
    )
    (net (code "88") (name "DDR_CH1_DM1_D") (class "Default")
      (node (ref "U1000") (pin "D22") (pinfunction "DDR_CH1_DM1_D_D22") (pintype "passive"))
    )
    (net (code "89") (name "DDR_CH1_DQ0_C") (class "Default")
      (node (ref "U1000") (pin "A8") (pinfunction "DDR_CH1_DQ0_C_A8") (pintype "passive"))
    )
    (net (code "90") (name "DDR_CH1_DQ0_D") (class "Default")
      (node (ref "U1000") (pin "A17") (pinfunction "DDR_CH1_DQ0_D_A17") (pintype "passive"))
    )
    (net (code "91") (name "DDR_CH1_DQ1_C") (class "Default")
      (node (ref "U1000") (pin "B9") (pinfunction "DDR_CH1_DQ1_C_B9") (pintype "passive"))
    )
    (net (code "92") (name "DDR_CH1_DQ1_D") (class "Default")
      (node (ref "U1000") (pin "B16") (pinfunction "DDR_CH1_DQ1_D_B16") (pintype "passive"))
    )
    (net (code "93") (name "DDR_CH1_DQ2_C") (class "Default")
      (node (ref "U1000") (pin "A9") (pinfunction "DDR_CH1_DQ2_C_A9") (pintype "passive"))
    )
    (net (code "94") (name "DDR_CH1_DQ2_D") (class "Default")
      (node (ref "U1000") (pin "A16") (pinfunction "DDR_CH1_DQ2_D_A16") (pintype "passive"))
    )
    (net (code "95") (name "DDR_CH1_DQ3_C") (class "Default")
      (node (ref "U1000") (pin "B10") (pinfunction "DDR_CH1_DQ3_C_B10") (pintype "passive"))
    )
    (net (code "96") (name "DDR_CH1_DQ3_D") (class "Default")
      (node (ref "U1000") (pin "B15") (pinfunction "DDR_CH1_DQ3_D_B15") (pintype "passive"))
    )
    (net (code "97") (name "DDR_CH1_DQ4_C") (class "Default")
      (node (ref "U1000") (pin "A6") (pinfunction "DDR_CH1_DQ4_C_A6") (pintype "passive"))
    )
    (net (code "98") (name "DDR_CH1_DQ4_D") (class "Default")
      (node (ref "U1000") (pin "A19") (pinfunction "DDR_CH1_DQ4_D_A19") (pintype "passive"))
    )
    (net (code "99") (name "DDR_CH1_DQ5_C") (class "Default")
      (node (ref "U1000") (pin "B7") (pinfunction "DDR_CH1_DQ5_C_B7") (pintype "passive"))
    )
    (net (code "100") (name "DDR_CH1_DQ5_D") (class "Default")
      (node (ref "U1000") (pin "B18") (pinfunction "DDR_CH1_DQ5_D_B18") (pintype "passive"))
    )
    (net (code "101") (name "DDR_CH1_DQ6_C") (class "Default")
      (node (ref "U1000") (pin "A7") (pinfunction "DDR_CH1_DQ6_C_A7") (pintype "passive"))
    )
    (net (code "102") (name "DDR_CH1_DQ6_D") (class "Default")
      (node (ref "U1000") (pin "A18") (pinfunction "DDR_CH1_DQ6_D_A18") (pintype "passive"))
    )
    (net (code "103") (name "DDR_CH1_DQ7_C") (class "Default")
      (node (ref "U1000") (pin "B8") (pinfunction "DDR_CH1_DQ7_C_B8") (pintype "passive"))
    )
    (net (code "104") (name "DDR_CH1_DQ7_D") (class "Default")
      (node (ref "U1000") (pin "B17") (pinfunction "DDR_CH1_DQ7_D_B17") (pintype "passive"))
    )
    (net (code "105") (name "DDR_CH1_DQ8_C") (class "Default")
      (node (ref "U1000") (pin "A3") (pinfunction "DDR_CH1_DQ8_C_A3") (pintype "passive"))
    )
    (net (code "106") (name "DDR_CH1_DQ8_D") (class "Default")
      (node (ref "U1000") (pin "A22") (pinfunction "DDR_CH1_DQ8_D_A22") (pintype "passive"))
    )
    (net (code "107") (name "DDR_CH1_DQ9_C") (class "Default")
      (node (ref "U1000") (pin "B3") (pinfunction "DDR_CH1_DQ9_C_B3") (pintype "passive"))
    )
    (net (code "108") (name "DDR_CH1_DQ9_D") (class "Default")
      (node (ref "U1000") (pin "B22") (pinfunction "DDR_CH1_DQ9_D_B22") (pintype "passive"))
    )
    (net (code "109") (name "DDR_CH1_DQ10_C") (class "Default")
      (node (ref "U1000") (pin "A2") (pinfunction "DDR_CH1_DQ10_C_A2") (pintype "passive"))
    )
    (net (code "110") (name "DDR_CH1_DQ10_D") (class "Default")
      (node (ref "U1000") (pin "A23") (pinfunction "DDR_CH1_DQ10_D_A23") (pintype "passive"))
    )
    (net (code "111") (name "DDR_CH1_DQ11_C") (class "Default")
      (node (ref "U1000") (pin "B2") (pinfunction "DDR_CH1_DQ11_C_B2") (pintype "passive"))
    )
    (net (code "112") (name "DDR_CH1_DQ11_D") (class "Default")
      (node (ref "U1000") (pin "B23") (pinfunction "DDR_CH1_DQ11_D_B23") (pintype "passive"))
    )
    (net (code "113") (name "DDR_CH1_DQ12_C") (class "Default")
      (node (ref "U1000") (pin "A5") (pinfunction "DDR_CH1_DQ12_C_A5") (pintype "passive"))
    )
    (net (code "114") (name "DDR_CH1_DQ12_D") (class "Default")
      (node (ref "U1000") (pin "A20") (pinfunction "DDR_CH1_DQ12_D_A20") (pintype "passive"))
    )
    (net (code "115") (name "DDR_CH1_DQ13_C") (class "Default")
      (node (ref "U1000") (pin "B5") (pinfunction "DDR_CH1_DQ13_C_B5") (pintype "passive"))
    )
    (net (code "116") (name "DDR_CH1_DQ13_D") (class "Default")
      (node (ref "U1000") (pin "B20") (pinfunction "DDR_CH1_DQ13_D_B20") (pintype "passive"))
    )
    (net (code "117") (name "DDR_CH1_DQ14_C") (class "Default")
      (node (ref "U1000") (pin "A4") (pinfunction "DDR_CH1_DQ14_C_A4") (pintype "passive"))
    )
    (net (code "118") (name "DDR_CH1_DQ14_D") (class "Default")
      (node (ref "U1000") (pin "A21") (pinfunction "DDR_CH1_DQ14_D_A21") (pintype "passive"))
    )
    (net (code "119") (name "DDR_CH1_DQ15_C") (class "Default")
      (node (ref "U1000") (pin "B4") (pinfunction "DDR_CH1_DQ15_C_B4") (pintype "passive"))
    )
    (net (code "120") (name "DDR_CH1_DQ15_D") (class "Default")
      (node (ref "U1000") (pin "B21") (pinfunction "DDR_CH1_DQ15_D_B21") (pintype "passive"))
    )
    (net (code "121") (name "DDR_CH1_DQS0N_C") (class "Default")
      (node (ref "U1000") (pin "D9") (pinfunction "DDR_CH1_DQS0N_C_D9") (pintype "passive"))
    )
    (net (code "122") (name "DDR_CH1_DQS0N_D") (class "Default")
      (node (ref "U1000") (pin "G16") (pinfunction "DDR_CH1_DQS0N_D_G16") (pintype "passive"))
    )
    (net (code "123") (name "DDR_CH1_DQS0P_C") (class "Default")
      (node (ref "U1000") (pin "E9") (pinfunction "DDR_CH1_DQS0P_C_E9") (pintype "passive"))
    )
    (net (code "124") (name "DDR_CH1_DQS0P_D") (class "Default")
      (node (ref "U1000") (pin "H16") (pinfunction "DDR_CH1_DQS0P_D_H16") (pintype "passive"))
    )
    (net (code "125") (name "DDR_CH1_DQS1N_C") (class "Default")
      (node (ref "U1000") (pin "D5") (pinfunction "DDR_CH1_DQS1N_C_D5") (pintype "passive"))
    )
    (net (code "126") (name "DDR_CH1_DQS1N_D") (class "Default")
      (node (ref "U1000") (pin "E21") (pinfunction "DDR_CH1_DQS1N_D_E21") (pintype "passive"))
    )
    (net (code "127") (name "DDR_CH1_DQS1P_C") (class "Default")
      (node (ref "U1000") (pin "E5") (pinfunction "DDR_CH1_DQS1P_C_E5") (pintype "passive"))
    )
    (net (code "128") (name "DDR_CH1_DQS1P_D") (class "Default")
      (node (ref "U1000") (pin "D21") (pinfunction "DDR_CH1_DQS1P_D_D21") (pintype "passive"))
    )
    (net (code "129") (name "DDR_CH1_LP4{slash}4X_CKE0{slash}LP5_CS0_C") (class "Default")
      (node (ref "U1000") (pin "D11") (pinfunction "DDR_CH1_LP4/4X_CKE0/LP5_CS0_C_D11") (pintype "passive"))
    )
    (net (code "130") (name "DDR_CH1_LP4{slash}4X_CKE0{slash}LP5_CS0_D") (class "Default")
      (node (ref "U1000") (pin "D16") (pinfunction "DDR_CH1_LP4/4X_CKE0/LP5_CS0_D_D16") (pintype "passive"))
    )
    (net (code "131") (name "DDR_CH1_LP4{slash}4X_CKE1{slash}LP5_CS1_C") (class "Default")
      (node (ref "U1000") (pin "E11") (pinfunction "DDR_CH1_LP4/4X_CKE1/LP5_CS1_C_E11") (pintype "passive"))
    )
    (net (code "132") (name "DDR_CH1_LP4{slash}4X_CKE1{slash}LP5_CS1_D") (class "Default")
      (node (ref "U1000") (pin "E16") (pinfunction "DDR_CH1_LP4/4X_CKE1/LP5_CS1_D_E16") (pintype "passive"))
    )
    (net (code "133") (name "DDR_CH1_LP4{slash}4X_CS0_C") (class "Default")
      (node (ref "U1000") (pin "G11") (pinfunction "DDR_CH1_LP4/4X_CS0_C_G11") (pintype "passive"))
    )
    (net (code "134") (name "DDR_CH1_LP4{slash}4X_CS0_D") (class "Default")
      (node (ref "U1000") (pin "E19") (pinfunction "DDR_CH1_LP4/4X_CS0_D_E19") (pintype "passive"))
    )
    (net (code "135") (name "DDR_CH1_LP4{slash}4X_CS1_C") (class "Default")
      (node (ref "U1000") (pin "H11") (pinfunction "DDR_CH1_LP4/4X_CS1_C_H11") (pintype "passive"))
    )
    (net (code "136") (name "DDR_CH1_LP4{slash}4X_CS1_D") (class "Default")
      (node (ref "U1000") (pin "D19") (pinfunction "DDR_CH1_LP4/4X_CS1_D_D19") (pintype "passive"))
    )
    (net (code "137") (name "DDR_RESET") (class "Default")
      (node (ref "U1000") (pin "T4") (pinfunction "DDR_CH0_RESET_A_T4") (pintype "passive"))
    )
    (net (code "138") (name "GND") (class "Default")
      (node (ref "C1200") (pin "2") (pinfunction "2_2") (pintype "passive"))
      (node (ref "C1201") (pin "2") (pinfunction "2_2") (pintype "passive"))
      (node (ref "C1202") (pin "2") (pinfunction "2_2") (pintype "passive"))
      (node (ref "C1203") (pin "2") (pinfunction "2_2") (pintype "passive"))
      (node (ref "C1204") (pin "2") (pinfunction "2_2") (pintype "passive"))
      (node (ref "C1205") (pin "2") (pinfunction "2_2") (pintype "passive"))
      (node (ref "C1206") (pin "2") (pinfunction "2_2") (pintype "passive"))
      (node (ref "C1207") (pin "2") (pinfunction "2_2") (pintype "passive"))
      (node (ref "C1208") (pin "2") (pinfunction "2_2") (pintype "passive"))
      (node (ref "C1209") (pin "2") (pinfunction "2_2") (pintype "passive"))
      (node (ref "C1210") (pin "2") (pinfunction "2_2") (pintype "passive"))
      (node (ref "C1211") (pin "2") (pinfunction "2_2") (pintype "passive"))
      (node (ref "C1212") (pin "2") (pinfunction "2_2") (pintype "passive"))
      (node (ref "C1213") (pin "2") (pinfunction "2_2") (pintype "passive"))
      (node (ref "C1214") (pin "2") (pinfunction "2_2") (pintype "passive"))
      (node (ref "C1215") (pin "2") (pinfunction "2_2") (pintype "passive"))
      (node (ref "C1216") (pin "2") (pinfunction "2_2") (pintype "passive"))
      (node (ref "C1217") (pin "2") (pinfunction "2_2") (pintype "passive"))
      (node (ref "C1218") (pin "2") (pinfunction "2_2") (pintype "passive"))
      (node (ref "C1219") (pin "2") (pinfunction "2_2") (pintype "passive"))
      (node (ref "C1220") (pin "2") (pinfunction "2_2") (pintype "passive"))
      (node (ref "C1221") (pin "2") (pinfunction "2_2") (pintype "passive"))
      (node (ref "C1223") (pin "2") (pinfunction "2_2") (pintype "passive"))
      (node (ref "C1224") (pin "2") (pinfunction "2_2") (pintype "passive"))
      (node (ref "C1225") (pin "2") (pinfunction "2_2") (pintype "passive"))
      (node (ref "C1226") (pin "2") (pinfunction "2_2") (pintype "passive"))
      (node (ref "C1227") (pin "2") (pinfunction "2_2") (pintype "passive"))
      (node (ref "C1228") (pin "2") (pinfunction "2_2") (pintype "passive"))
      (node (ref "C1229") (pin "2") (pinfunction "2_2") (pintype "passive"))
      (node (ref "C1231") (pin "2") (pinfunction "2_2") (pintype "passive"))
      (node (ref "C1232") (pin "2") (pinfunction "2_2") (pintype "passive"))
      (node (ref "U1000") (pin "L16") (pinfunction "DDR_CH1_PLL_AVSS_L16") (pintype "power_in"))
      (node (ref "U1000") (pin "M11") (pinfunction "DDR_CH0_PLL_AVSS_M11") (pintype "power_in"))
    )
    (net (code "139") (name "Net-(U1000A-DDR_CH0_ZQ_A)") (class "Default")
      (node (ref "R1200") (pin "2") (pinfunction "2_2") (pintype "passive"))
      (node (ref "U1000") (pin "W8") (pinfunction "DDR_CH0_ZQ_A_W8") (pintype "passive"))
    )
    (net (code "140") (name "Net-(U1000A-DDR_CH0_ZQ_B)") (class "Default")
      (node (ref "R1201") (pin "1") (pinfunction "1_1") (pintype "passive"))
      (node (ref "U1000") (pin "H7") (pinfunction "DDR_CH0_ZQ_B_H7") (pintype "passive"))
    )
    (net (code "141") (name "Net-(U1000B-DDR_CH1_ZQ_C)") (class "Default")
      (node (ref "R1202") (pin "2") (pinfunction "2_2") (pintype "passive"))
      (node (ref "U1000") (pin "G8") (pinfunction "DDR_CH1_ZQ_C_G8") (pintype "passive"))
    )
    (net (code "142") (name "Net-(U1000B-DDR_CH1_ZQ_D)") (class "Default")
      (node (ref "R1203") (pin "1") (pinfunction "1_1") (pintype "passive"))
      (node (ref "U1000") (pin "F18") (pinfunction "DDR_CH1_ZQ_D_F18") (pintype "passive"))
    )
    (net (code "143") (name "VCCA_1V8") (class "Default")
      (node (ref "C1214") (pin "1") (pinfunction "1_1") (pintype "passive"))
      (node (ref "C1217") (pin "1") (pinfunction "1_1") (pintype "passive"))
      (node (ref "U1000") (pin "K16") (pinfunction "DDR_CH1_PLL_AVDD1V8_K16") (pintype "power_in"))
      (node (ref "U1000") (pin "M12") (pinfunction "DDR_CH0_PLL_AVDD1V8_M12") (pintype "power_in"))
    )
    (net (code "144") (name "VDD2_DDR") (class "Default")
      (node (ref "R1205") (pin "2") (pinfunction "2_2") (pintype "passive"))
    )
    (net (code "145") (name "VDD2_DDR_CKE") (class "Default")
      (node (ref "C1216") (pin "1") (pinfunction "1_1") (pintype "passive"))
      (node (ref "C1219") (pin "1") (pinfunction "1_1") (pintype "passive"))
      (node (ref "R1205") (pin "1") (pinfunction "1_1") (pintype "passive"))
      (node (ref "U1000") (pin "H13") (pinfunction "DDR_CH1_VDDQ_CKE_H13") (pintype "power_in"))
      (node (ref "U1000") (pin "N8") (pinfunction "DDR_CH0_VDDQ_CKE_N8") (pintype "power_in"))
    )
    (net (code "146") (name "VDDA_DDR_PLL") (class "Default")
      (node (ref "C1215") (pin "1") (pinfunction "1_1") (pintype "passive"))
      (node (ref "C1218") (pin "1") (pinfunction "1_1") (pintype "passive"))
      (node (ref "U1000") (pin "L15") (pinfunction "DDR_CH1_PLL_DVDD_L15") (pintype "power_in"))
      (node (ref "U1000") (pin "N12") (pinfunction "DDR_CH0_PLL_DVDD_N12") (pintype "power_in"))
    )
    (net (code "147") (name "VDDQ_DDR") (class "Default")
      (node (ref "C1200") (pin "1") (pinfunction "1_1") (pintype "passive"))
      (node (ref "C1201") (pin "1") (pinfunction "1_1") (pintype "passive"))
      (node (ref "C1202") (pin "1") (pinfunction "1_1") (pintype "passive"))
      (node (ref "C1203") (pin "1") (pinfunction "1_1") (pintype "passive"))
      (node (ref "C1204") (pin "1") (pinfunction "1_1") (pintype "passive"))
      (node (ref "C1205") (pin "1") (pinfunction "1_1") (pintype "passive"))
      (node (ref "C1207") (pin "1") (pinfunction "1_1") (pintype "passive"))
      (node (ref "C1208") (pin "1") (pinfunction "1_1") (pintype "passive"))
      (node (ref "C1209") (pin "1") (pinfunction "1_1") (pintype "passive"))
      (node (ref "C1210") (pin "1") (pinfunction "1_1") (pintype "passive"))
      (node (ref "C1211") (pin "1") (pinfunction "1_1") (pintype "passive"))
      (node (ref "C1212") (pin "1") (pinfunction "1_1") (pintype "passive"))
      (node (ref "R1200") (pin "1") (pinfunction "1_1") (pintype "passive"))
      (node (ref "R1201") (pin "2") (pinfunction "2_2") (pintype "passive"))
      (node (ref "R1202") (pin "1") (pinfunction "1_1") (pintype "passive"))
      (node (ref "R1203") (pin "2") (pinfunction "2_2") (pintype "passive"))
      (node (ref "R1204") (pin "2") (pinfunction "2_2") (pintype "passive"))
      (node (ref "U1000") (pin "K11") (pinfunction "DDR_CH1_VDDQ_0_K11") (pintype "power_in"))
      (node (ref "U1000") (pin "K12") (pinfunction "DDR_CH1_VDDQ_1_K12") (pintype "power_in"))
      (node (ref "U1000") (pin "K13") (pinfunction "DDR_CH1_VDDQ_2_K13") (pintype "power_in"))
      (node (ref "U1000") (pin "K14") (pinfunction "DDR_CH1_VDDQ_3_K14") (pintype "power_in"))
      (node (ref "U1000") (pin "K15") (pinfunction "DDR_CH1_VDDQ_4_K15") (pintype "power_in"))
      (node (ref "U1000") (pin "M10") (pinfunction "DDR_CH0_VDDQ_0_M10") (pintype "power_in"))
      (node (ref "U1000") (pin "N10") (pinfunction "DDR_CH0_VDDQ_1_N10") (pintype "power_in"))
      (node (ref "U1000") (pin "P10") (pinfunction "DDR_CH0_VDDQ_2_P10") (pintype "power_in"))
      (node (ref "U1000") (pin "R10") (pinfunction "DDR_CH0_VDDQ_3_R10") (pintype "power_in"))
      (node (ref "U1000") (pin "T10") (pinfunction "DDR_CH0_VDDQ_4_T10") (pintype "power_in"))
    )
    (net (code "148") (name "VDDQ_DDR_CK") (class "Default")
      (node (ref "C1206") (pin "1") (pinfunction "1_1") (pintype "passive"))
      (node (ref "C1213") (pin "1") (pinfunction "1_1") (pintype "passive"))
      (node (ref "C1232") (pin "1") (pinfunction "1_1") (pintype "passive"))
      (node (ref "R1204") (pin "1") (pinfunction "1_1") (pintype "passive"))
      (node (ref "U1000") (pin "L10") (pinfunction "DDR_CH0_VDDQ_CK_L10") (pintype "power_in"))
      (node (ref "U1000") (pin "M13") (pinfunction "DDR_CH1_VDDQ_CK_M13") (pintype "power_in"))
    )
    (net (code "149") (name "VDD_DDR") (class "Default")
      (node (ref "C1220") (pin "1") (pinfunction "1_1") (pintype "passive"))
      (node (ref "C1221") (pin "1") (pinfunction "1_1") (pintype "passive"))
      (node (ref "C1223") (pin "1") (pinfunction "1_1") (pintype "passive"))
      (node (ref "C1224") (pin "1") (pinfunction "1_1") (pintype "passive"))
      (node (ref "C1225") (pin "1") (pinfunction "1_1") (pintype "passive"))
      (node (ref "C1226") (pin "1") (pinfunction "1_1") (pintype "passive"))
      (node (ref "C1227") (pin "1") (pinfunction "1_1") (pintype "passive"))
      (node (ref "C1228") (pin "1") (pinfunction "1_1") (pintype "passive"))
      (node (ref "C1229") (pin "1") (pinfunction "1_1") (pintype "passive"))
      (node (ref "C1231") (pin "1") (pinfunction "1_1") (pintype "passive"))
      (node (ref "U1000") (pin "L11") (pinfunction "DDR_CH1_VDD_0_L11") (pintype "power_in"))
      (node (ref "U1000") (pin "L12") (pinfunction "DDR_CH1_VDD_1_L12") (pintype "power_in"))
      (node (ref "U1000") (pin "L13") (pinfunction "DDR_CH1_VDD_2_L13") (pintype "power_in"))
      (node (ref "U1000") (pin "L14") (pinfunction "DDR_CH1_VDD_3_L14") (pintype "power_in"))
      (node (ref "U1000") (pin "L17") (pinfunction "DDR_CH1_VDD_MIF_0_L17") (pintype "power_in"))
      (node (ref "U1000") (pin "L18") (pinfunction "DDR_CH1_VDD_MIF_1_L18") (pintype "power_in"))
      (node (ref "U1000") (pin "N13") (pinfunction "DDR_CH0_VDD_MIF_0_N13") (pintype "power_in"))
      (node (ref "U1000") (pin "P12") (pinfunction "DDR_CH0_VDD_3_P12") (pintype "power_in"))
      (node (ref "U1000") (pin "P13") (pinfunction "DDR_CH0_VDD_MIF_1_P13") (pintype "power_in"))
      (node (ref "U1000") (pin "R12") (pinfunction "DDR_CH0_VDD_2_R12") (pintype "power_in"))
      (node (ref "U1000") (pin "T12") (pinfunction "DDR_CH0_VDD_1_T12") (pintype "power_in"))
      (node (ref "U1000") (pin "U11") (pinfunction "DDR_CH0_VDD_0_U11") (pintype "power_in"))
    )
    (net (code "150") (name "unconnected-(U1000A-DDR_CH0_A6_A-PadT5)") (class "Default")
      (node (ref "U1000") (pin "T5") (pinfunction "DDR_CH0_A6_A_T5") (pintype "passive+no_connect"))
    )
    (net (code "151") (name "unconnected-(U1000A-DDR_CH0_A6_B-PadM7)") (class "Default")
      (node (ref "U1000") (pin "M7") (pinfunction "DDR_CH0_A6_B_M7") (pintype "passive+no_connect"))
    )
    (net (code "152") (name "unconnected-(U1000A-DDR_CH0_RESET_B-PadK7)") (class "Default")
      (node (ref "U1000") (pin "K7") (pinfunction "DDR_CH0_RESET_B_K7") (pintype "passive+no_connect"))
    )
    (net (code "153") (name "unconnected-(U1000A-DDR_CH0_WCK0N_A-PadV6)") (class "Default")
      (node (ref "U1000") (pin "V6") (pinfunction "DDR_CH0_WCK0N_A_V6") (pintype "passive+no_connect"))
    )
    (net (code "154") (name "unconnected-(U1000A-DDR_CH0_WCK0N_B-PadK4)") (class "Default")
      (node (ref "U1000") (pin "K4") (pinfunction "DDR_CH0_WCK0N_B_K4") (pintype "passive+no_connect"))
    )
    (net (code "155") (name "unconnected-(U1000A-DDR_CH0_WCK0P_A-PadV7)") (class "Default")
      (node (ref "U1000") (pin "V7") (pinfunction "DDR_CH0_WCK0P_A_V7") (pintype "passive+no_connect"))
    )
    (net (code "156") (name "unconnected-(U1000A-DDR_CH0_WCK0P_B-PadK5)") (class "Default")
      (node (ref "U1000") (pin "K5") (pinfunction "DDR_CH0_WCK0P_B_K5") (pintype "passive+no_connect"))
    )
    (net (code "157") (name "unconnected-(U1000A-DDR_CH0_WCK1N_A-PadW5)") (class "Default")
      (node (ref "U1000") (pin "W5") (pinfunction "DDR_CH0_WCK1N_A_W5") (pintype "passive+no_connect"))
    )
    (net (code "158") (name "unconnected-(U1000A-DDR_CH0_WCK1N_B-PadH5)") (class "Default")
      (node (ref "U1000") (pin "H5") (pinfunction "DDR_CH0_WCK1N_B_H5") (pintype "passive+no_connect"))
    )
    (net (code "159") (name "unconnected-(U1000A-DDR_CH0_WCK1P_A-PadW4)") (class "Default")
      (node (ref "U1000") (pin "W4") (pinfunction "DDR_CH0_WCK1P_A_W4") (pintype "passive+no_connect"))
    )
    (net (code "160") (name "unconnected-(U1000A-DDR_CH0_WCK1P_B-PadH4)") (class "Default")
      (node (ref "U1000") (pin "H4") (pinfunction "DDR_CH0_WCK1P_B_H4") (pintype "passive+no_connect"))
    )
    (net (code "161") (name "unconnected-(U1000B-DDR_CH1_A6_C-PadD10)") (class "Default")
      (node (ref "U1000") (pin "D10") (pinfunction "DDR_CH1_A6_C_D10") (pintype "passive+no_connect"))
    )
    (net (code "162") (name "unconnected-(U1000B-DDR_CH1_A6_D-PadD14)") (class "Default")
      (node (ref "U1000") (pin "D14") (pinfunction "DDR_CH1_A6_D_D14") (pintype "passive+no_connect"))
    )
    (net (code "163") (name "unconnected-(U1000B-DDR_CH1_RESET_C-PadE10)") (class "Default")
      (node (ref "U1000") (pin "E10") (pinfunction "DDR_CH1_RESET_C_E10") (pintype "passive+no_connect"))
    )
    (net (code "164") (name "unconnected-(U1000B-DDR_CH1_RESET_D-PadC19)") (class "Default")
      (node (ref "U1000") (pin "C19") (pinfunction "DDR_CH1_RESET_D_C19") (pintype "passive+no_connect"))
    )
    (net (code "165") (name "unconnected-(U1000B-DDR_CH1_WCK0N_C-PadH9)") (class "Default")
      (node (ref "U1000") (pin "H9") (pinfunction "DDR_CH1_WCK0N_C_H9") (pintype "passive+no_connect"))
    )
    (net (code "166") (name "unconnected-(U1000B-DDR_CH1_WCK0N_D-PadD17)") (class "Default")
      (node (ref "U1000") (pin "D17") (pinfunction "DDR_CH1_WCK0N_D_D17") (pintype "passive+no_connect"))
    )
    (net (code "167") (name "unconnected-(U1000B-DDR_CH1_WCK0P_C-PadG9)") (class "Default")
      (node (ref "U1000") (pin "G9") (pinfunction "DDR_CH1_WCK0P_C_G9") (pintype "passive+no_connect"))
    )
    (net (code "168") (name "unconnected-(U1000B-DDR_CH1_WCK0P_D-PadE17)") (class "Default")
      (node (ref "U1000") (pin "E17") (pinfunction "DDR_CH1_WCK0P_D_E17") (pintype "passive+no_connect"))
    )
    (net (code "169") (name "unconnected-(U1000B-DDR_CH1_WCK1N_C-PadE7)") (class "Default")
      (node (ref "U1000") (pin "E7") (pinfunction "DDR_CH1_WCK1N_C_E7") (pintype "passive+no_connect"))
    )
    (net (code "170") (name "unconnected-(U1000B-DDR_CH1_WCK1N_D-PadG18)") (class "Default")
      (node (ref "U1000") (pin "G18") (pinfunction "DDR_CH1_WCK1N_D_G18") (pintype "passive+no_connect"))
    )
    (net (code "171") (name "unconnected-(U1000B-DDR_CH1_WCK1P_C-PadD7)") (class "Default")
      (node (ref "U1000") (pin "D7") (pinfunction "DDR_CH1_WCK1P_C_D7") (pintype "passive+no_connect"))
    )
    (net (code "172") (name "unconnected-(U1000B-DDR_CH1_WCK1P_D-PadH18)") (class "Default")
      (node (ref "U1000") (pin "H18") (pinfunction "DDR_CH1_WCK1P_D_H18") (pintype "passive+no_connect"))
    )
  )
)
